# SK3000v2_-_FINAL.net
KiCad netlist of a schematic drawn in EAGLE
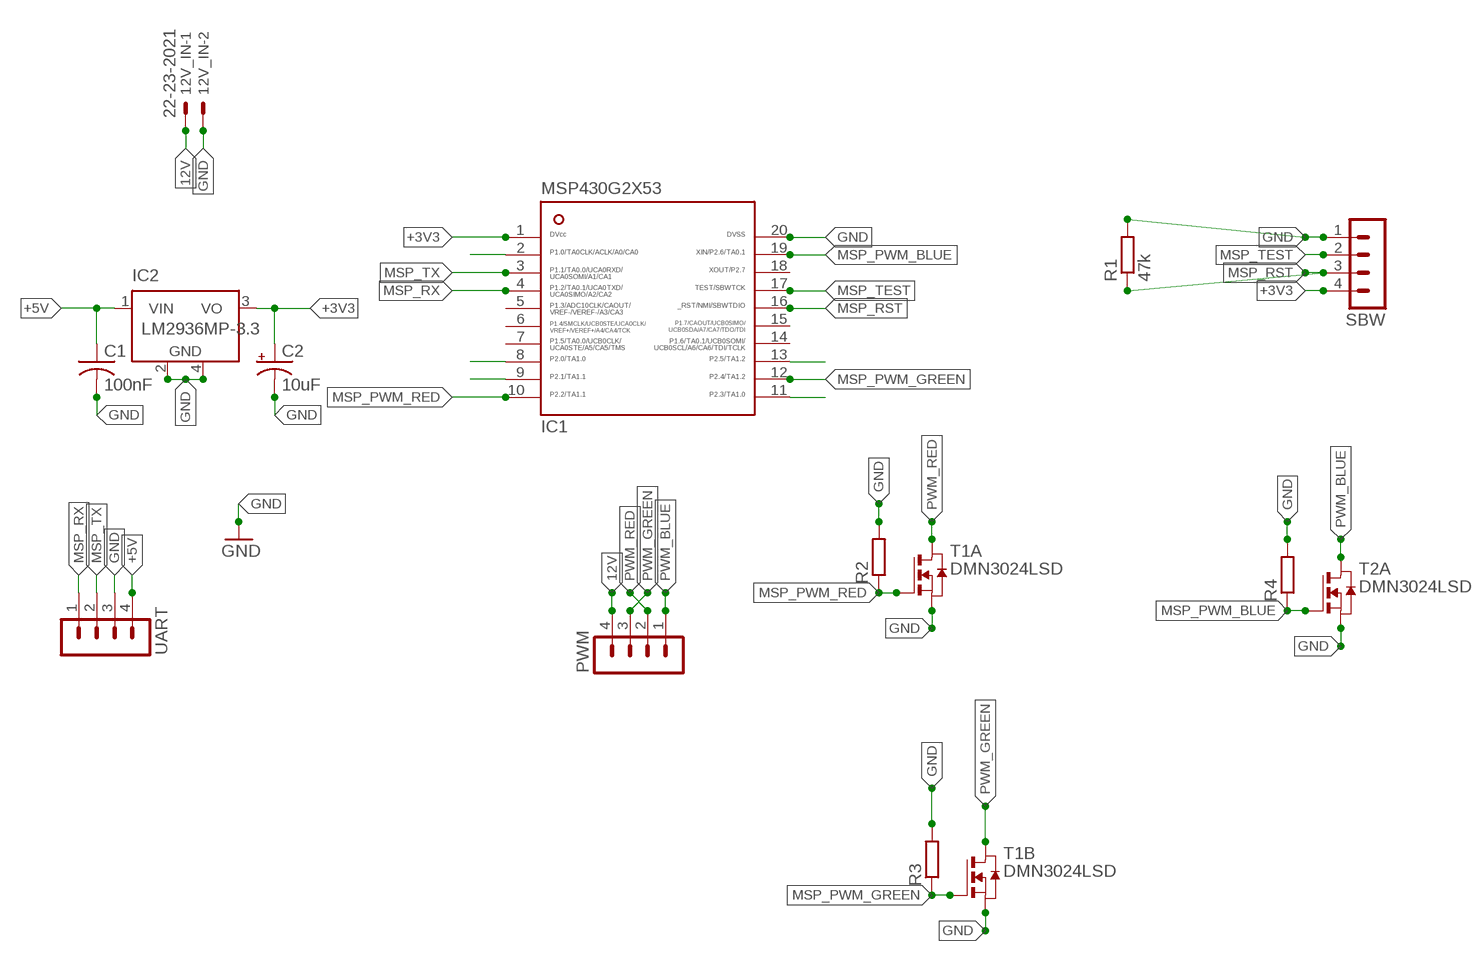
[diagram p0: schematic, sheet 1]

(export (version "E")
  (design (tool "Eeschema 10.0.6"))
  (components
    (comp (ref "12V_IN")
      (value "22-23-2021")
      (footprint "eagle-import:22-23-2021")
      (fields (field (name "MF") "MOLEX"))
      (libsource (lib "eagle-import") (part "22-23-2021"))
    )
    (comp (ref "C1")
      (value "100nF")
      (footprint "eagle-import:C025-024X044")
      (libsource (lib "eagle-import") (part "C-US025-024X044"))
    )
    (comp (ref "C2")
      (value "10uF")
      (footprint "eagle-import:E2,5-5")
      (libsource (lib "eagle-import") (part "CPOL-USE2.5-5"))
    )
    (comp (ref "IC1")
      (value "MSP430G2553")
      (footprint "eagle-import:PW20")
      (libsource (lib "eagle-import") (part "MSP430G2X53-20PW20"))
    )
    (comp (ref "IC2")
      (value "LM2936MP-3.3")
      (footprint "eagle-import:SOT223")
      (fields (field (name "MF") "NATIONAL SEMICONDUCTOR") (field (name "MPN") "LM2936MP-3.3/NOPB"))
      (libsource (lib "eagle-import") (part "LM2936MP?-3.3"))
    )
    (comp (ref "PWM")
      (value "MA04-1")
      (footprint "eagle-import:MA04-1")
      (libsource (lib "eagle-import") (part "MA04-1"))
    )
    (comp (ref "R1")
      (value "47k")
      (footprint "eagle-import:0207_5V")
      (libsource (lib "eagle-import") (part "R-EU_0207/5V"))
    )
    (comp (ref "R2")
      (value "R-EU_0207/5V")
      (footprint "eagle-import:0207_5V")
      (libsource (lib "eagle-import") (part "R-EU_0207/5V"))
    )
    (comp (ref "R3")
      (value "R-EU_0207/5V")
      (footprint "eagle-import:0207_5V")
      (libsource (lib "eagle-import") (part "R-EU_0207/5V"))
    )
    (comp (ref "R4")
      (value "R-EU_0207/5V")
      (footprint "eagle-import:0207_5V")
      (libsource (lib "eagle-import") (part "R-EU_0207/5V"))
    )
    (comp (ref "SBW")
      (value "MA04-1")
      (footprint "eagle-import:MA04-1")
      (libsource (lib "eagle-import") (part "MA04-1"))
    )
    (comp (ref "T1")
      (value "DMN3024LSD")
      (footprint "eagle-import:SO8")
      (libsource (lib "eagle-import") (part "DMN3024LSD"))
    )
    (comp (ref "T2")
      (value "DMN3024LSD")
      (footprint "eagle-import:SO8")
      (libsource (lib "eagle-import") (part "DMN3024LSD"))
    )
    (comp (ref "UART")
      (value "MA04-1")
      (footprint "eagle-import:MA04-1")
      (libsource (lib "eagle-import") (part "MA04-1"))
    )
  )
  (nets
    (net (code "1") (name "+3V3") (class "Default")
      (node (ref "C2") (pin "+") (pinfunction "+_+") (pintype "passive"))
      (node (ref "IC1") (pin "1") (pinfunction "1_1") (pintype "bidirectional"))
      (node (ref "IC2") (pin "3") (pinfunction "VO_3") (pintype "passive"))
      (node (ref "SBW") (pin "4") (pinfunction "4_4") (pintype "passive"))
    )
    (net (code "2") (name "+5V") (class "Default")
      (node (ref "C1") (pin "1") (pinfunction "1_1") (pintype "passive"))
      (node (ref "IC2") (pin "1") (pinfunction "VIN_1") (pintype "input"))
      (node (ref "UART") (pin "4") (pinfunction "4_4") (pintype "passive"))
    )
    (net (code "3") (name "12V") (class "Default")
      (node (ref "12V_IN") (pin "1") (pinfunction "S_1") (pintype "passive"))
      (node (ref "PWM") (pin "4") (pinfunction "4_4") (pintype "passive"))
    )
    (net (code "4") (name "GND") (class "Default")
      (node (ref "12V_IN") (pin "2") (pinfunction "S_2") (pintype "passive"))
      (node (ref "C1") (pin "2") (pinfunction "2_2") (pintype "passive"))
      (node (ref "C2") (pin "-") (pinfunction "-_-") (pintype "passive"))
      (node (ref "IC1") (pin "20") (pinfunction "20_20") (pintype "bidirectional"))
      (node (ref "IC2") (pin "2") (pinfunction "GND_2") (pintype "passive"))
      (node (ref "IC2") (pin "4") (pinfunction "GND_4") (pintype "passive"))
      (node (ref "R1") (pin "2") (pinfunction "2_2") (pintype "passive"))
      (node (ref "R2") (pin "2") (pinfunction "2_2") (pintype "passive"))
      (node (ref "R3") (pin "2") (pinfunction "2_2") (pintype "passive"))
      (node (ref "R4") (pin "2") (pinfunction "2_2") (pintype "passive"))
      (node (ref "SBW") (pin "1") (pinfunction "1_1") (pintype "passive"))
      (node (ref "T1") (pin "1") (pinfunction "S_1") (pintype "passive"))
      (node (ref "T1") (pin "3") (pinfunction "S_3") (pintype "passive"))
      (node (ref "T2") (pin "1") (pinfunction "S_1") (pintype "passive"))
      (node (ref "UART") (pin "3") (pinfunction "3_3") (pintype "passive"))
    )
    (net (code "5") (name "MSP_PWM_BLUE") (class "Default")
      (node (ref "IC1") (pin "19") (pinfunction "19_19") (pintype "bidirectional"))
      (node (ref "R4") (pin "1") (pinfunction "1_1") (pintype "passive"))
      (node (ref "T2") (pin "2") (pinfunction "G_2") (pintype "passive"))
    )
    (net (code "6") (name "MSP_PWM_GREEN") (class "Default")
      (node (ref "IC1") (pin "12") (pinfunction "12_12") (pintype "bidirectional"))
      (node (ref "R3") (pin "1") (pinfunction "1_1") (pintype "passive"))
      (node (ref "T1") (pin "4") (pinfunction "G_4") (pintype "passive"))
    )
    (net (code "7") (name "MSP_PWM_RED") (class "Default")
      (node (ref "IC1") (pin "10") (pinfunction "10_10") (pintype "bidirectional"))
      (node (ref "R2") (pin "1") (pinfunction "1_1") (pintype "passive"))
      (node (ref "T1") (pin "2") (pinfunction "G_2") (pintype "passive"))
    )
    (net (code "8") (name "MSP_RST") (class "Default")
      (node (ref "IC1") (pin "16") (pinfunction "16_16") (pintype "bidirectional"))
      (node (ref "R1") (pin "1") (pinfunction "1_1") (pintype "passive"))
      (node (ref "SBW") (pin "3") (pinfunction "3_3") (pintype "passive"))
    )
    (net (code "9") (name "MSP_RX") (class "Default")
      (node (ref "IC1") (pin "4") (pinfunction "4_4") (pintype "bidirectional"))
      (node (ref "UART") (pin "1") (pinfunction "1_1") (pintype "passive"))
    )
    (net (code "10") (name "MSP_TEST") (class "Default")
      (node (ref "IC1") (pin "17") (pinfunction "17_17") (pintype "bidirectional"))
      (node (ref "SBW") (pin "2") (pinfunction "2_2") (pintype "passive"))
    )
    (net (code "11") (name "MSP_TX") (class "Default")
      (node (ref "IC1") (pin "3") (pinfunction "3_3") (pintype "bidirectional"))
      (node (ref "UART") (pin "2") (pinfunction "2_2") (pintype "passive"))
    )
    (net (code "12") (name "PWM_BLUE") (class "Default")
      (node (ref "PWM") (pin "1") (pinfunction "1_1") (pintype "passive"))
      (node (ref "T2") (pin "7") (pinfunction "D_7") (pintype "passive"))
      (node (ref "T2") (pin "8") (pinfunction "D_8") (pintype "passive"))
    )
    (net (code "13") (name "PWM_GREEN") (class "Default")
      (node (ref "PWM") (pin "3") (pinfunction "3_3") (pintype "passive"))
      (node (ref "T1") (pin "5") (pinfunction "D_5") (pintype "passive"))
      (node (ref "T1") (pin "6") (pinfunction "D_6") (pintype "passive"))
    )
    (net (code "14") (name "PWM_RED") (class "Default")
      (node (ref "PWM") (pin "2") (pinfunction "2_2") (pintype "passive"))
      (node (ref "T1") (pin "7") (pinfunction "D_7") (pintype "passive"))
      (node (ref "T1") (pin "8") (pinfunction "D_8") (pintype "passive"))
    )
    (net (code "15") (name "unconnected-(IC1-Pad2)") (class "Default")
      (node (ref "IC1") (pin "2") (pinfunction "2_2") (pintype "bidirectional"))
    )
    (net (code "16") (name "unconnected-(IC1-Pad5)") (class "Default")
      (node (ref "IC1") (pin "5") (pinfunction "5_5") (pintype "bidirectional"))
    )
    (net (code "17") (name "unconnected-(IC1-Pad6)") (class "Default")
      (node (ref "IC1") (pin "6") (pinfunction "6_6") (pintype "bidirectional"))
    )
    (net (code "18") (name "unconnected-(IC1-Pad7)") (class "Default")
      (node (ref "IC1") (pin "7") (pinfunction "7_7") (pintype "bidirectional"))
    )
    (net (code "19") (name "unconnected-(IC1-Pad8)") (class "Default")
      (node (ref "IC1") (pin "8") (pinfunction "8_8") (pintype "bidirectional"))
    )
    (net (code "20") (name "unconnected-(IC1-Pad9)") (class "Default")
      (node (ref "IC1") (pin "9") (pinfunction "9_9") (pintype "bidirectional"))
    )
    (net (code "21") (name "unconnected-(IC1-Pad11)") (class "Default")
      (node (ref "IC1") (pin "11") (pinfunction "11_11") (pintype "bidirectional"))
    )
    (net (code "22") (name "unconnected-(IC1-Pad13)") (class "Default")
      (node (ref "IC1") (pin "13") (pinfunction "13_13") (pintype "bidirectional"))
    )
    (net (code "23") (name "unconnected-(IC1-Pad14)") (class "Default")
      (node (ref "IC1") (pin "14") (pinfunction "14_14") (pintype "bidirectional"))
    )
    (net (code "24") (name "unconnected-(IC1-Pad15)") (class "Default")
      (node (ref "IC1") (pin "15") (pinfunction "15_15") (pintype "bidirectional"))
    )
    (net (code "25") (name "unconnected-(IC1-Pad18)") (class "Default")
      (node (ref "IC1") (pin "18") (pinfunction "18_18") (pintype "bidirectional"))
    )
  )
)
